# Monophase.net
KiCad netlist of a schematic drawn in EAGLE
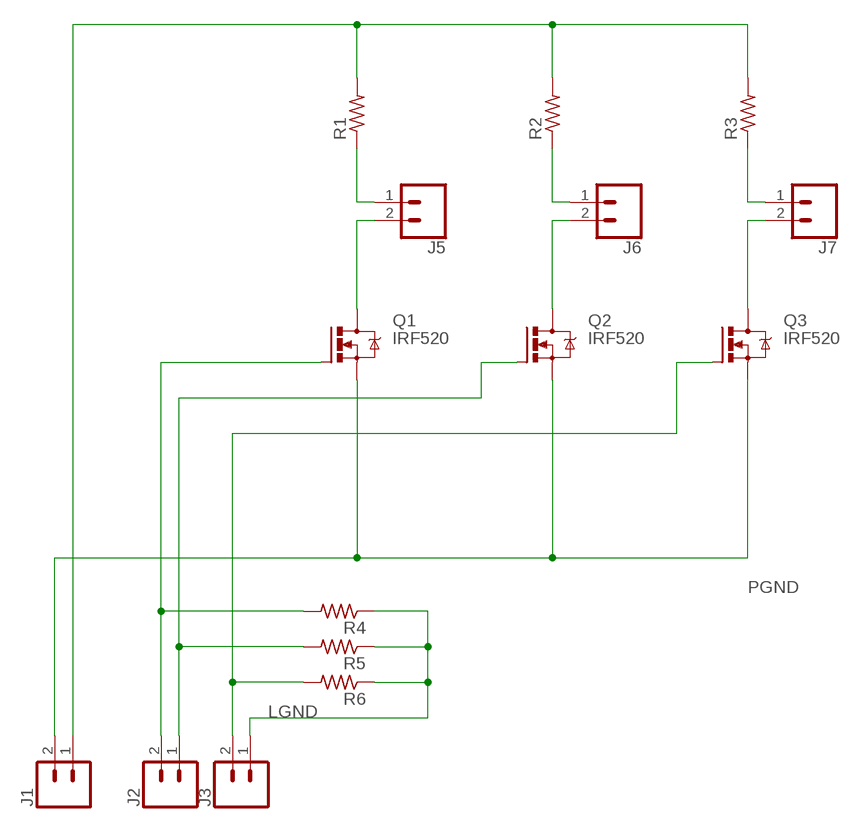
[diagram p0: schematic, sheet 1]

(export (version "E")
  (design (tool "Eeschema 10.0.6"))
  (components
    (comp (ref "J1")
      (value "CONN_02POLAR_LOCK")
      (footprint "eagle-import:MOLEX-1X2_LOCK")
      (libsource (lib "eagle-import") (part "CONN_02POLAR_LOCK"))
    )
    (comp (ref "J2")
      (value "CONN_02POLAR_LOCK")
      (footprint "eagle-import:MOLEX-1X2_LOCK")
      (libsource (lib "eagle-import") (part "CONN_02POLAR_LOCK"))
    )
    (comp (ref "J3")
      (value "CONN_02POLAR_LOCK")
      (footprint "eagle-import:MOLEX-1X2_LOCK")
      (libsource (lib "eagle-import") (part "CONN_02POLAR_LOCK"))
    )
    (comp (ref "J5")
      (value "CONN_02POLAR_LOCK")
      (footprint "eagle-import:MOLEX-1X2_LOCK")
      (libsource (lib "eagle-import") (part "CONN_02POLAR_LOCK"))
    )
    (comp (ref "J6")
      (value "CONN_02POLAR_LOCK")
      (footprint "eagle-import:MOLEX-1X2_LOCK")
      (libsource (lib "eagle-import") (part "CONN_02POLAR_LOCK"))
    )
    (comp (ref "J7")
      (value "CONN_02POLAR_LOCK")
      (footprint "eagle-import:MOLEX-1X2_LOCK")
      (libsource (lib "eagle-import") (part "CONN_02POLAR_LOCK"))
    )
    (comp (ref "Q1")
      (value "IRF520")
      (footprint "eagle-import:TO220BV")
      (libsource (lib "eagle-import") (part "IRF520"))
    )
    (comp (ref "Q2")
      (value "IRF520")
      (footprint "eagle-import:TO220BV")
      (libsource (lib "eagle-import") (part "IRF520"))
    )
    (comp (ref "Q3")
      (value "IRF520")
      (footprint "eagle-import:TO220BV")
      (libsource (lib "eagle-import") (part "IRF520"))
    )
    (comp (ref "R1")
      (value "R-US_0204/7")
      (footprint "eagle-import:0204_7")
      (libsource (lib "eagle-import") (part "R-US_0204/7"))
    )
    (comp (ref "R2")
      (value "R-US_0204/7")
      (footprint "eagle-import:0204_7")
      (libsource (lib "eagle-import") (part "R-US_0204/7"))
    )
    (comp (ref "R3")
      (value "R-US_0204/7")
      (footprint "eagle-import:0204_7")
      (libsource (lib "eagle-import") (part "R-US_0204/7"))
    )
    (comp (ref "R4")
      (value "R-US_0204/7")
      (footprint "eagle-import:0204_7")
      (libsource (lib "eagle-import") (part "R-US_0204/7"))
    )
    (comp (ref "R5")
      (value "R-US_0204/7")
      (footprint "eagle-import:0204_7")
      (libsource (lib "eagle-import") (part "R-US_0204/7"))
    )
    (comp (ref "R6")
      (value "R-US_0204/7")
      (footprint "eagle-import:0204_7")
      (libsource (lib "eagle-import") (part "R-US_0204/7"))
    )
  )
  (nets
    (net (code "1") (name "/LGND") (class "Default")
      (node (ref "J3") (pin "1") (pinfunction "1_1") (pintype "passive"))
      (node (ref "R4") (pin "1") (pinfunction "1_1") (pintype "passive"))
      (node (ref "R5") (pin "1") (pinfunction "1_1") (pintype "passive"))
      (node (ref "R6") (pin "1") (pinfunction "1_1") (pintype "passive"))
    )
    (net (code "2") (name "/PGND") (class "Default")
      (node (ref "J1") (pin "2") (pinfunction "2_2") (pintype "passive"))
      (node (ref "Q1") (pin "S") (pinfunction "S_S") (pintype "passive"))
      (node (ref "Q2") (pin "S") (pinfunction "S_S") (pintype "passive"))
      (node (ref "Q3") (pin "S") (pinfunction "S_S") (pintype "passive"))
    )
    (net (code "3") (name "Net-(J1-Pad1)") (class "Default")
      (node (ref "J1") (pin "1") (pinfunction "1_1") (pintype "passive"))
      (node (ref "R1") (pin "2") (pinfunction "2_2") (pintype "passive"))
      (node (ref "R2") (pin "2") (pinfunction "2_2") (pintype "passive"))
      (node (ref "R3") (pin "2") (pinfunction "2_2") (pintype "passive"))
    )
    (net (code "4") (name "Net-(J2-Pad1)") (class "Default")
      (node (ref "J2") (pin "1") (pinfunction "1_1") (pintype "passive"))
      (node (ref "Q2") (pin "G") (pinfunction "G_G") (pintype "passive"))
      (node (ref "R5") (pin "2") (pinfunction "2_2") (pintype "passive"))
    )
    (net (code "5") (name "Net-(J2-Pad2)") (class "Default")
      (node (ref "J2") (pin "2") (pinfunction "2_2") (pintype "passive"))
      (node (ref "Q1") (pin "G") (pinfunction "G_G") (pintype "passive"))
      (node (ref "R4") (pin "2") (pinfunction "2_2") (pintype "passive"))
    )
    (net (code "6") (name "Net-(J3-Pad2)") (class "Default")
      (node (ref "J3") (pin "2") (pinfunction "2_2") (pintype "passive"))
      (node (ref "Q3") (pin "G") (pinfunction "G_G") (pintype "passive"))
      (node (ref "R6") (pin "2") (pinfunction "2_2") (pintype "passive"))
    )
    (net (code "7") (name "Net-(J5-Pad1)") (class "Default")
      (node (ref "J5") (pin "1") (pinfunction "1_1") (pintype "passive"))
      (node (ref "R1") (pin "1") (pinfunction "1_1") (pintype "passive"))
    )
    (net (code "8") (name "Net-(J5-Pad2)") (class "Default")
      (node (ref "J5") (pin "2") (pinfunction "2_2") (pintype "passive"))
      (node (ref "Q1") (pin "D") (pinfunction "D_D") (pintype "passive"))
    )
    (net (code "9") (name "Net-(J6-Pad1)") (class "Default")
      (node (ref "J6") (pin "1") (pinfunction "1_1") (pintype "passive"))
      (node (ref "R2") (pin "1") (pinfunction "1_1") (pintype "passive"))
    )
    (net (code "10") (name "Net-(J6-Pad2)") (class "Default")
      (node (ref "J6") (pin "2") (pinfunction "2_2") (pintype "passive"))
      (node (ref "Q2") (pin "D") (pinfunction "D_D") (pintype "passive"))
    )
    (net (code "11") (name "Net-(J7-Pad1)") (class "Default")
      (node (ref "J7") (pin "1") (pinfunction "1_1") (pintype "passive"))
      (node (ref "R3") (pin "1") (pinfunction "1_1") (pintype "passive"))
    )
    (net (code "12") (name "Net-(J7-Pad2)") (class "Default")
      (node (ref "J7") (pin "2") (pinfunction "2_2") (pintype "passive"))
      (node (ref "Q3") (pin "D") (pinfunction "D_D") (pintype "passive"))
    )
  )
)
